# SwitchDemoESeries.net
KiCad netlist of a schematic drawn in EAGLE
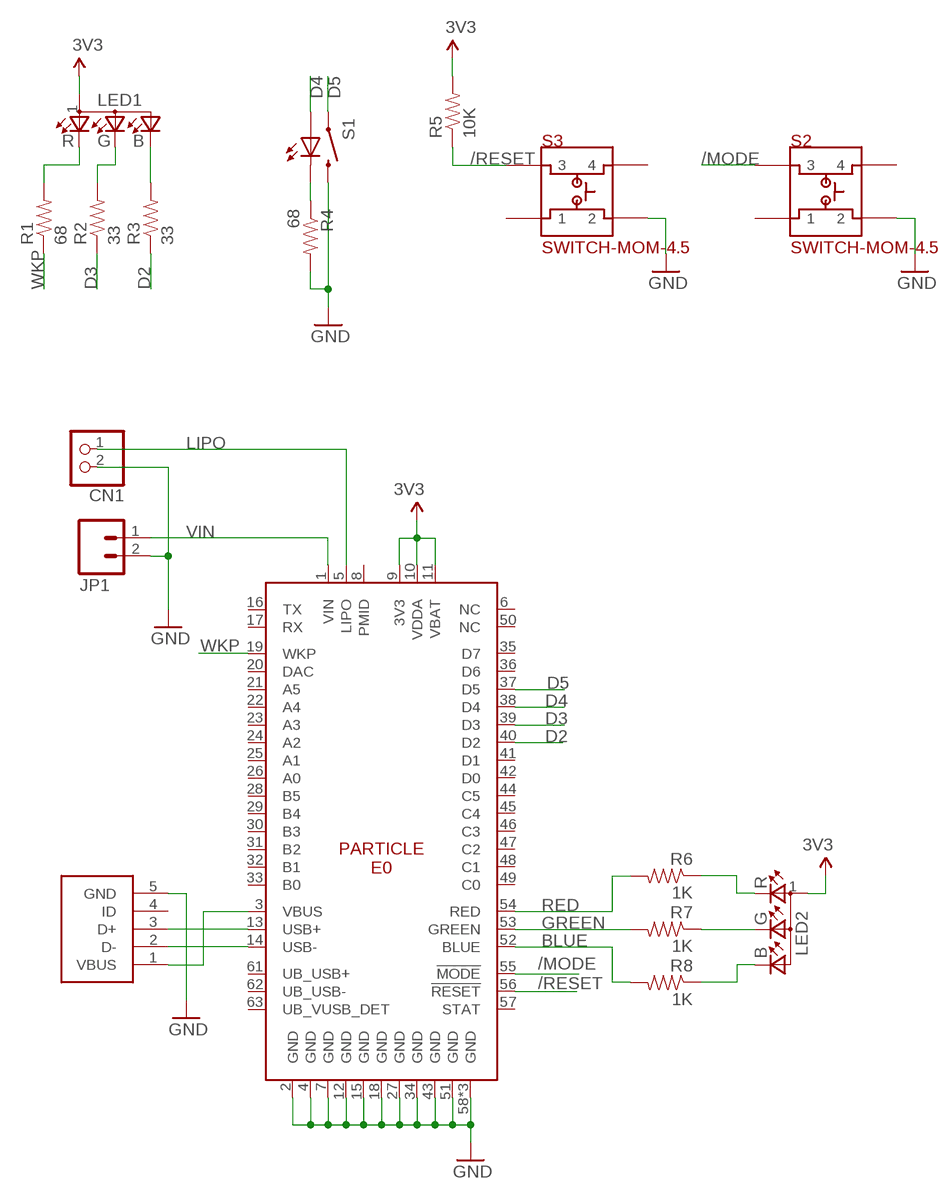
[diagram p0: schematic, sheet 1]

(export (version "E")
  (design (tool "Eeschema 10.0.6"))
  (components
    (comp (ref "CN1")
      (value "JST_2PIN-THM")
      (footprint "eagle-import:JST-PH-2-THM")
      (libsource (lib "eagle-import") (part "JST_2PIN-THM"))
    )
    (comp (ref "JP1")
      (value "M02PTH")
      (footprint "eagle-import:1X02")
      (libsource (lib "eagle-import") (part "M02PTH"))
    )
    (comp (ref "LED1")
      (value "LED-RGB-CREE-SMD")
      (footprint "eagle-import:LED-RGB-CREE-SMD")
      (libsource (lib "eagle-import") (part "LED-RGB-CREE-SMD"))
    )
    (comp (ref "LED2")
      (value "LED-RGB-CREE-SMD")
      (footprint "eagle-import:LED-RGB-CREE-SMD")
      (libsource (lib "eagle-import") (part "LED-RGB-CREE-SMD"))
    )
    (comp (ref "R1")
      (value "68")
      (footprint "eagle-import:0603-RES")
      (libsource (lib "eagle-import") (part "RES-68-0603.DEV"))
    )
    (comp (ref "R2")
      (value "33")
      (footprint "eagle-import:0603-RES")
      (libsource (lib "eagle-import") (part "RES-33-0603.DEV"))
    )
    (comp (ref "R3")
      (value "33")
      (footprint "eagle-import:0603-RES")
      (libsource (lib "eagle-import") (part "RES-33-0603.DEV"))
    )
    (comp (ref "R4")
      (value "68")
      (footprint "eagle-import:0603-RES")
      (libsource (lib "eagle-import") (part "RES-68-0603.DEV"))
    )
    (comp (ref "R5")
      (value "10K")
      (footprint "eagle-import:0603-RES")
      (libsource (lib "eagle-import") (part "RES-10K-06030603"))
    )
    (comp (ref "R6")
      (value "1K")
      (footprint "eagle-import:0603-RES")
      (libsource (lib "eagle-import") (part "RES-1K-0603"))
    )
    (comp (ref "R7")
      (value "1K")
      (footprint "eagle-import:0603-RES")
      (libsource (lib "eagle-import") (part "RES-1K-0603"))
    )
    (comp (ref "R8")
      (value "1K")
      (footprint "eagle-import:0603-RES")
      (libsource (lib "eagle-import") (part "RES-1K-0603"))
    )
    (comp (ref "S1")
      (value "SWITCH-MOMENTARY-LEDPTH")
      (footprint "eagle-import:TACTILE-PTH-LED-12MM")
      (libsource (lib "eagle-import") (part "SWITCH-MOMENTARY-LEDPTH"))
    )
    (comp (ref "S2")
      (value "SWITCH-MOM-4.5")
      (footprint "eagle-import:SWITCH-MOM-4.5")
      (libsource (lib "eagle-import") (part "SWITCH-MOM-4.5"))
    )
    (comp (ref "S3")
      (value "SWITCH-MOM-4.5")
      (footprint "eagle-import:SWITCH-MOM-4.5")
      (libsource (lib "eagle-import") (part "SWITCH-MOM-4.5"))
    )
    (comp (ref "U$3")
      (value "USB-MICRO-B-SOCKET-AMPHENOL")
      (footprint "eagle-import:USB-B-SMT-AMPHENOL")
      (libsource (lib "eagle-import") (part "USB-MICRO-B-SOCKET-AMPHENOL"))
    )
    (comp (ref "U1")
      (value "E0_V005")
      (footprint "eagle-import:E0")
      (libsource (lib "eagle-import") (part "E0_V005"))
    )
  )
  (nets
    (net (code "1") (name "/BLUE") (class "Default")
      (node (ref "R8") (pin "2") (pinfunction "2_2") (pintype "passive"))
      (node (ref "U1") (pin "52") (pinfunction "BLUE_52") (pintype "bidirectional"))
    )
    (net (code "2") (name "/D2") (class "Default")
      (node (ref "R3") (pin "1") (pinfunction "1_1") (pintype "passive"))
      (node (ref "U1") (pin "40") (pinfunction "D2_40") (pintype "bidirectional"))
    )
    (net (code "3") (name "/D3") (class "Default")
      (node (ref "R2") (pin "1") (pinfunction "1_1") (pintype "passive"))
      (node (ref "U1") (pin "39") (pinfunction "D3_39") (pintype "bidirectional"))
    )
    (net (code "4") (name "/D4") (class "Default")
      (node (ref "S1") (pin "A") (pinfunction "A_A") (pintype "passive"))
      (node (ref "U1") (pin "38") (pinfunction "D4_38") (pintype "bidirectional"))
    )
    (net (code "5") (name "/D5") (class "Default")
      (node (ref "S1") (pin "4") (pinfunction "1_4") (pintype "passive"))
      (node (ref "U1") (pin "37") (pinfunction "D5_37") (pintype "bidirectional"))
    )
    (net (code "6") (name "/GREEN") (class "Default")
      (node (ref "R7") (pin "2") (pinfunction "2_2") (pintype "passive"))
      (node (ref "U1") (pin "53") (pinfunction "GREEN_53") (pintype "bidirectional"))
    )
    (net (code "7") (name "/LIPO") (class "Default")
      (node (ref "CN1") (pin "1") (pinfunction "2_1") (pintype "passive"))
      (node (ref "U1") (pin "5") (pinfunction "LIPO_5") (pintype "bidirectional"))
    )
    (net (code "8") (name "/RED") (class "Default")
      (node (ref "R6") (pin "2") (pinfunction "2_2") (pintype "passive"))
      (node (ref "U1") (pin "54") (pinfunction "RED_54") (pintype "bidirectional"))
    )
    (net (code "9") (name "/VIN") (class "Default")
      (node (ref "JP1") (pin "1") (pinfunction "1_1") (pintype "passive"))
      (node (ref "U1") (pin "1") (pinfunction "VIN_1") (pintype "bidirectional"))
    )
    (net (code "10") (name "/WKP") (class "Default")
      (node (ref "R1") (pin "1") (pinfunction "1_1") (pintype "passive"))
      (node (ref "U1") (pin "19") (pinfunction "WKP_19") (pintype "bidirectional"))
    )
    (net (code "11") (name "/{slash}MODE") (class "Default")
      (node (ref "S2") (pin "3") (pinfunction "3_3") (pintype "passive"))
      (node (ref "U1") (pin "55") (pinfunction "~{MODE}_55") (pintype "bidirectional"))
    )
    (net (code "12") (name "/{slash}RESET") (class "Default")
      (node (ref "R5") (pin "1") (pinfunction "1_1") (pintype "passive"))
      (node (ref "S3") (pin "3") (pinfunction "3_3") (pintype "passive"))
      (node (ref "U1") (pin "56") (pinfunction "~{RESET}_56") (pintype "bidirectional"))
    )
    (net (code "13") (name "3V3") (class "Default")
      (node (ref "LED1") (pin "1") (pinfunction "A_1") (pintype "passive"))
      (node (ref "LED2") (pin "1") (pinfunction "A_1") (pintype "passive"))
      (node (ref "R5") (pin "2") (pinfunction "2_2") (pintype "passive"))
      (node (ref "U1") (pin "10") (pinfunction "VDDA_10") (pintype "bidirectional"))
      (node (ref "U1") (pin "11") (pinfunction "VBAT_11") (pintype "bidirectional"))
      (node (ref "U1") (pin "9") (pinfunction "3V3_9") (pintype "bidirectional"))
    )
    (net (code "14") (name "GND") (class "Default")
      (node (ref "CN1") (pin "2") (pinfunction "1_2") (pintype "passive"))
      (node (ref "JP1") (pin "2") (pinfunction "2_2") (pintype "passive"))
      (node (ref "R4") (pin "2") (pinfunction "2_2") (pintype "passive"))
      (node (ref "S1") (pin "2") (pinfunction "2_2") (pintype "passive"))
      (node (ref "S2") (pin "2") (pinfunction "2_2") (pintype "passive"))
      (node (ref "S3") (pin "2") (pinfunction "2_2") (pintype "passive"))
      (node (ref "U$3") (pin "5") (pinfunction "GND_5") (pintype "passive"))
      (node (ref "U1") (pin "12") (pinfunction "GND_12") (pintype "bidirectional"))
      (node (ref "U1") (pin "15") (pinfunction "GND_15") (pintype "bidirectional"))
      (node (ref "U1") (pin "18") (pinfunction "GND_18") (pintype "bidirectional"))
      (node (ref "U1") (pin "2") (pinfunction "GND_2") (pintype "bidirectional"))
      (node (ref "U1") (pin "27") (pinfunction "GND_27") (pintype "bidirectional"))
      (node (ref "U1") (pin "34") (pinfunction "GND_34") (pintype "bidirectional"))
      (node (ref "U1") (pin "4") (pinfunction "GND_4") (pintype "bidirectional"))
      (node (ref "U1") (pin "43") (pinfunction "GND_43") (pintype "bidirectional"))
      (node (ref "U1") (pin "51") (pinfunction "GND_51") (pintype "bidirectional"))
      (node (ref "U1") (pin "58") (pinfunction "GND_58") (pintype "bidirectional"))
      (node (ref "U1") (pin "59") (pinfunction "GND_59") (pintype "bidirectional"))
      (node (ref "U1") (pin "60") (pinfunction "GND_60") (pintype "bidirectional"))
      (node (ref "U1") (pin "7") (pinfunction "GND_7") (pintype "bidirectional"))
    )
    (net (code "15") (name "Net-(LED1-B)") (class "Default")
      (node (ref "LED1") (pin "2") (pinfunction "B_2") (pintype "passive"))
      (node (ref "R3") (pin "2") (pinfunction "2_2") (pintype "passive"))
    )
    (net (code "16") (name "Net-(LED1-G)") (class "Default")
      (node (ref "LED1") (pin "3") (pinfunction "G_3") (pintype "passive"))
      (node (ref "R2") (pin "2") (pinfunction "2_2") (pintype "passive"))
    )
    (net (code "17") (name "Net-(LED1-R)") (class "Default")
      (node (ref "LED1") (pin "4") (pinfunction "R_4") (pintype "passive"))
      (node (ref "R1") (pin "2") (pinfunction "2_2") (pintype "passive"))
    )
    (net (code "18") (name "Net-(LED2-B)") (class "Default")
      (node (ref "LED2") (pin "2") (pinfunction "B_2") (pintype "passive"))
      (node (ref "R8") (pin "1") (pinfunction "1_1") (pintype "passive"))
    )
    (net (code "19") (name "Net-(LED2-G)") (class "Default")
      (node (ref "LED2") (pin "3") (pinfunction "G_3") (pintype "passive"))
      (node (ref "R7") (pin "1") (pinfunction "1_1") (pintype "passive"))
    )
    (net (code "20") (name "Net-(LED2-R)") (class "Default")
      (node (ref "LED2") (pin "4") (pinfunction "R_4") (pintype "passive"))
      (node (ref "R6") (pin "1") (pinfunction "1_1") (pintype "passive"))
    )
    (net (code "21") (name "Net-(R4-Pad1)") (class "Default")
      (node (ref "R4") (pin "1") (pinfunction "1_1") (pintype "passive"))
      (node (ref "S1") (pin "C") (pinfunction "C_C") (pintype "passive"))
    )
    (net (code "22") (name "Net-(U$3-D+)") (class "Default")
      (node (ref "U$3") (pin "3") (pinfunction "D+_3") (pintype "passive"))
      (node (ref "U1") (pin "13") (pinfunction "USB+_13") (pintype "bidirectional"))
    )
    (net (code "23") (name "Net-(U$3-D-)") (class "Default")
      (node (ref "U$3") (pin "2") (pinfunction "D-_2") (pintype "passive"))
      (node (ref "U1") (pin "14") (pinfunction "USB-_14") (pintype "bidirectional"))
    )
    (net (code "24") (name "Net-(U$3-VBUS)") (class "Default")
      (node (ref "U$3") (pin "1") (pinfunction "VBUS_1") (pintype "passive"))
      (node (ref "U1") (pin "3") (pinfunction "VBUS_3") (pintype "bidirectional"))
    )
    (net (code "25") (name "unconnected-(S2-Pad1)") (class "Default")
      (node (ref "S2") (pin "1") (pinfunction "1_1") (pintype "passive"))
    )
    (net (code "26") (name "unconnected-(S2-Pad4)") (class "Default")
      (node (ref "S2") (pin "4") (pinfunction "4_4") (pintype "passive"))
    )
    (net (code "27") (name "unconnected-(S3-Pad1)") (class "Default")
      (node (ref "S3") (pin "1") (pinfunction "1_1") (pintype "passive"))
    )
    (net (code "28") (name "unconnected-(S3-Pad4)") (class "Default")
      (node (ref "S3") (pin "4") (pinfunction "4_4") (pintype "passive"))
    )
    (net (code "29") (name "unconnected-(U$3-ID-Pad4)") (class "Default")
      (node (ref "U$3") (pin "4") (pinfunction "ID_4") (pintype "passive"))
    )
    (net (code "30") (name "unconnected-(U1-A0-Pad26)") (class "Default")
      (node (ref "U1") (pin "26") (pinfunction "A0_26") (pintype "bidirectional"))
    )
    (net (code "31") (name "unconnected-(U1-A1-Pad25)") (class "Default")
      (node (ref "U1") (pin "25") (pinfunction "A1_25") (pintype "bidirectional"))
    )
    (net (code "32") (name "unconnected-(U1-A2-Pad24)") (class "Default")
      (node (ref "U1") (pin "24") (pinfunction "A2_24") (pintype "bidirectional"))
    )
    (net (code "33") (name "unconnected-(U1-A3-Pad23)") (class "Default")
      (node (ref "U1") (pin "23") (pinfunction "A3_23") (pintype "bidirectional"))
    )
    (net (code "34") (name "unconnected-(U1-A4-Pad22)") (class "Default")
      (node (ref "U1") (pin "22") (pinfunction "A4_22") (pintype "bidirectional"))
    )
    (net (code "35") (name "unconnected-(U1-A5-Pad21)") (class "Default")
      (node (ref "U1") (pin "21") (pinfunction "A5_21") (pintype "bidirectional"))
    )
    (net (code "36") (name "unconnected-(U1-B0-Pad33)") (class "Default")
      (node (ref "U1") (pin "33") (pinfunction "B0_33") (pintype "bidirectional"))
    )
    (net (code "37") (name "unconnected-(U1-B1-Pad32)") (class "Default")
      (node (ref "U1") (pin "32") (pinfunction "B1_32") (pintype "bidirectional"))
    )
    (net (code "38") (name "unconnected-(U1-B2-Pad31)") (class "Default")
      (node (ref "U1") (pin "31") (pinfunction "B2_31") (pintype "bidirectional"))
    )
    (net (code "39") (name "unconnected-(U1-B3-Pad30)") (class "Default")
      (node (ref "U1") (pin "30") (pinfunction "B3_30") (pintype "bidirectional"))
    )
    (net (code "40") (name "unconnected-(U1-B4-Pad29)") (class "Default")
      (node (ref "U1") (pin "29") (pinfunction "B4_29") (pintype "bidirectional"))
    )
    (net (code "41") (name "unconnected-(U1-B5-Pad28)") (class "Default")
      (node (ref "U1") (pin "28") (pinfunction "B5_28") (pintype "bidirectional"))
    )
    (net (code "42") (name "unconnected-(U1-C0-Pad49)") (class "Default")
      (node (ref "U1") (pin "49") (pinfunction "C0_49") (pintype "bidirectional"))
    )
    (net (code "43") (name "unconnected-(U1-C1-Pad48)") (class "Default")
      (node (ref "U1") (pin "48") (pinfunction "C1_48") (pintype "bidirectional"))
    )
    (net (code "44") (name "unconnected-(U1-C2-Pad47)") (class "Default")
      (node (ref "U1") (pin "47") (pinfunction "C2_47") (pintype "bidirectional"))
    )
    (net (code "45") (name "unconnected-(U1-C3-Pad46)") (class "Default")
      (node (ref "U1") (pin "46") (pinfunction "C3_46") (pintype "bidirectional"))
    )
    (net (code "46") (name "unconnected-(U1-C4-Pad45)") (class "Default")
      (node (ref "U1") (pin "45") (pinfunction "C4_45") (pintype "bidirectional"))
    )
    (net (code "47") (name "unconnected-(U1-C5-Pad44)") (class "Default")
      (node (ref "U1") (pin "44") (pinfunction "C5_44") (pintype "bidirectional"))
    )
    (net (code "48") (name "unconnected-(U1-D0-Pad42)") (class "Default")
      (node (ref "U1") (pin "42") (pinfunction "D0_42") (pintype "bidirectional"))
    )
    (net (code "49") (name "unconnected-(U1-D1-Pad41)") (class "Default")
      (node (ref "U1") (pin "41") (pinfunction "D1_41") (pintype "bidirectional"))
    )
    (net (code "50") (name "unconnected-(U1-D6-Pad36)") (class "Default")
      (node (ref "U1") (pin "36") (pinfunction "D6_36") (pintype "bidirectional"))
    )
    (net (code "51") (name "unconnected-(U1-D7-Pad35)") (class "Default")
      (node (ref "U1") (pin "35") (pinfunction "D7_35") (pintype "bidirectional"))
    )
    (net (code "52") (name "unconnected-(U1-DAC-Pad20)") (class "Default")
      (node (ref "U1") (pin "20") (pinfunction "DAC_20") (pintype "bidirectional"))
    )
    (net (code "53") (name "unconnected-(U1-NC-Pad6)") (class "Default")
      (node (ref "U1") (pin "6") (pinfunction "NC_6") (pintype "bidirectional"))
    )
    (net (code "54") (name "unconnected-(U1-NC-Pad50)") (class "Default")
      (node (ref "U1") (pin "50") (pinfunction "NC_50") (pintype "bidirectional"))
    )
    (net (code "55") (name "unconnected-(U1-PMID-Pad8)") (class "Default")
      (node (ref "U1") (pin "8") (pinfunction "PMID_8") (pintype "bidirectional"))
    )
    (net (code "56") (name "unconnected-(U1-RX-Pad17)") (class "Default")
      (node (ref "U1") (pin "17") (pinfunction "RX_17") (pintype "bidirectional"))
    )
    (net (code "57") (name "unconnected-(U1-STAT-Pad57)") (class "Default")
      (node (ref "U1") (pin "57") (pinfunction "STAT_57") (pintype "bidirectional"))
    )
    (net (code "58") (name "unconnected-(U1-TX-Pad16)") (class "Default")
      (node (ref "U1") (pin "16") (pinfunction "TX_16") (pintype "bidirectional"))
    )
    (net (code "59") (name "unconnected-(U1-UB_USB+-Pad61)") (class "Default")
      (node (ref "U1") (pin "61") (pinfunction "UB_USB+_61") (pintype "bidirectional"))
    )
    (net (code "60") (name "unconnected-(U1-UB_USB--Pad62)") (class "Default")
      (node (ref "U1") (pin "62") (pinfunction "UB_USB-_62") (pintype "bidirectional"))
    )
    (net (code "61") (name "unconnected-(U1-UB_VUSB_DET-Pad63)") (class "Default")
      (node (ref "U1") (pin "63") (pinfunction "UB_VUSB_DET_63") (pintype "bidirectional"))
    )
  )
)
